# slave-basic.net
KiCad netlist of a schematic drawn in EAGLE
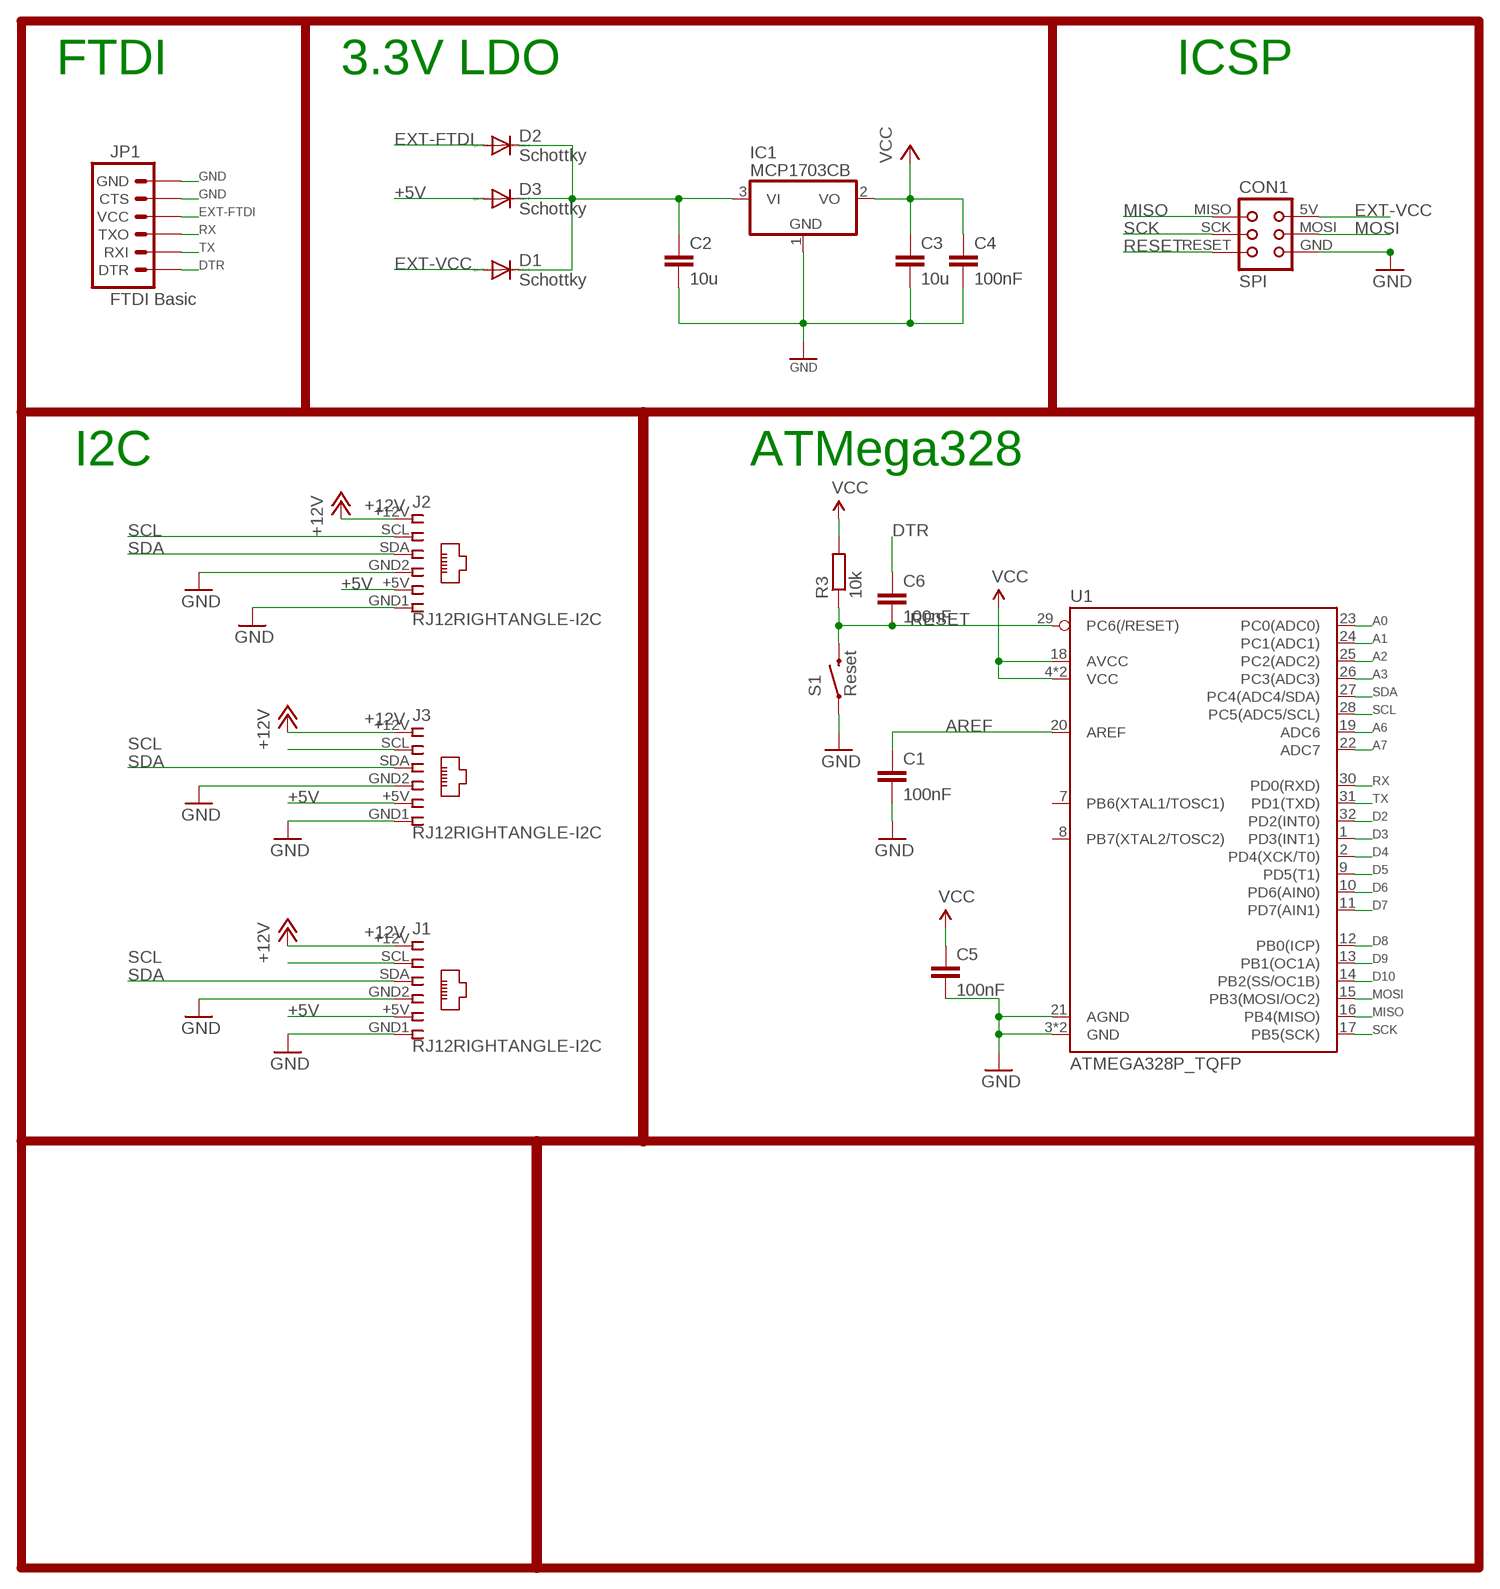
[diagram p0: schematic, sheet 1]

(export (version "E")
  (design (tool "Eeschema 10.0.6"))
  (components
    (comp (ref "C1")
      (value "100nF")
      (footprint "eagle-import:C0805K")
      (fields (field (name "MPN") "80-C1206C104K5R"))
      (libsource (lib "eagle-import") (part "C-EUC0805K"))
    )
    (comp (ref "C2")
      (value "10u")
      (footprint "eagle-import:C0805K")
      (fields (field (name "MPN") "77-VJ1206V106ZXQTBC"))
      (libsource (lib "eagle-import") (part "C-EUC0805K"))
    )
    (comp (ref "C3")
      (value "10u")
      (footprint "eagle-import:C0805K")
      (fields (field (name "MPN") "77-VJ1206V106ZXQTBC"))
      (libsource (lib "eagle-import") (part "C-EUC0805K"))
    )
    (comp (ref "C4")
      (value "100nF")
      (footprint "eagle-import:C0805K")
      (fields (field (name "MPN") "80-C1206C104K5R"))
      (libsource (lib "eagle-import") (part "C-EUC0805K"))
    )
    (comp (ref "C5")
      (value "100nF")
      (footprint "eagle-import:C0805K")
      (fields (field (name "MPN") "80-C1206C104K5R"))
      (libsource (lib "eagle-import") (part "C-EUC0805K"))
    )
    (comp (ref "C6")
      (value "100nF")
      (footprint "eagle-import:C0805K")
      (fields (field (name "MPN") "80-C1206C104K5R"))
      (libsource (lib "eagle-import") (part "C-EUC0805K"))
    )
    (comp (ref "CON1")
      (value "SPI")
      (footprint "eagle-import:TC2030-MCP")
      (libsource (lib "eagle-import") (part "TINYISPTAG"))
    )
    (comp (ref "D1")
      (value "Schottky")
      (footprint "eagle-import:SOD123")
      (fields (field (name "MPN") "621-1N5819HW-F"))
      (libsource (lib "eagle-import") (part "MBR0520LT"))
    )
    (comp (ref "D2")
      (value "Schottky")
      (footprint "eagle-import:SOD123")
      (fields (field (name "MPN") "621-1N5819HW-F"))
      (libsource (lib "eagle-import") (part "MBR0520LT"))
    )
    (comp (ref "D3")
      (value "Schottky")
      (footprint "eagle-import:SOD123")
      (fields (field (name "MPN") "621-1N5819HW-F"))
      (libsource (lib "eagle-import") (part "MBR0520LT"))
    )
    (comp (ref "IC1")
      (value "MCP1703CB")
      (footprint "eagle-import:SOT23")
      (libsource (lib "eagle-import") (part "MCP1703CB"))
    )
    (comp (ref "J1")
      (value "RJ12RIGHTANGLE-I2C")
      (footprint "eagle-import:RJ12-RIGHTANGLE-I2C")
      (libsource (lib "eagle-import") (part "RJ12RIGHTANGLE-I2C"))
    )
    (comp (ref "J2")
      (value "RJ12RIGHTANGLE-I2C")
      (footprint "eagle-import:RJ12-RIGHTANGLE-I2C")
      (libsource (lib "eagle-import") (part "RJ12RIGHTANGLE-I2C"))
    )
    (comp (ref "J3")
      (value "RJ12RIGHTANGLE-I2C")
      (footprint "eagle-import:RJ12-RIGHTANGLE-I2C")
      (libsource (lib "eagle-import") (part "RJ12RIGHTANGLE-I2C"))
    )
    (comp (ref "JP1")
      (value "FTDI Basic")
      (footprint "eagle-import:1X06")
      (libsource (lib "eagle-import") (part "ARDUINO_SERIAL_PROGRAMPTH"))
    )
    (comp (ref "R3")
      (value "10k")
      (footprint "eagle-import:R0805")
      (libsource (lib "eagle-import") (part "R-EU_R0805"))
    )
    (comp (ref "S1")
      (value "Reset")
      (footprint "eagle-import:TACTILE-SWITCH-SMD-ALT01")
      (libsource (lib "eagle-import") (part "SWITCH-MOMENTARY-2SMD-ALT01"))
    )
    (comp (ref "U1")
      (value "ATMEGA328P_TQFP")
      (footprint "eagle-import:TQFP32-08")
      (libsource (lib "eagle-import") (part "ATMEGA328P_TQFP"))
    )
  )
  (nets
    (net (code "1") (name "+12V") (class "Default")
      (node (ref "J1") (pin "+12V") (pinfunction "1_+12V") (pintype "bidirectional"))
      (node (ref "J2") (pin "+12V") (pinfunction "1_+12V") (pintype "bidirectional"))
      (node (ref "J3") (pin "+12V") (pinfunction "1_+12V") (pintype "bidirectional"))
    )
    (net (code "2") (name "/+5V") (class "Default")
      (node (ref "D3") (pin "A") (pinfunction "A_A") (pintype "passive"))
      (node (ref "J1") (pin "+5V") (pinfunction "5_+5V") (pintype "bidirectional"))
      (node (ref "J2") (pin "+5V") (pinfunction "5_+5V") (pintype "bidirectional"))
      (node (ref "J3") (pin "+5V") (pinfunction "5_+5V") (pintype "bidirectional"))
    )
    (net (code "3") (name "/A0") (class "Default")
      (node (ref "U1") (pin "23") (pinfunction "PC0(ADC0)_23") (pintype "bidirectional"))
    )
    (net (code "4") (name "/A1") (class "Default")
      (node (ref "U1") (pin "24") (pinfunction "PC1(ADC1)_24") (pintype "bidirectional"))
    )
    (net (code "5") (name "/A2") (class "Default")
      (node (ref "U1") (pin "25") (pinfunction "PC2(ADC2)_25") (pintype "bidirectional"))
    )
    (net (code "6") (name "/A3") (class "Default")
      (node (ref "U1") (pin "26") (pinfunction "PC3(ADC3)_26") (pintype "bidirectional"))
    )
    (net (code "7") (name "/A6") (class "Default")
      (node (ref "U1") (pin "19") (pinfunction "ADC6_19") (pintype "bidirectional"))
    )
    (net (code "8") (name "/A7") (class "Default")
      (node (ref "U1") (pin "22") (pinfunction "ADC7_22") (pintype "bidirectional"))
    )
    (net (code "9") (name "/AREF") (class "Default")
      (node (ref "C1") (pin "1") (pinfunction "1_1") (pintype "passive"))
      (node (ref "U1") (pin "20") (pinfunction "AREF_20") (pintype "bidirectional"))
    )
    (net (code "10") (name "/D2") (class "Default")
      (node (ref "U1") (pin "32") (pinfunction "PD2(INT0)_32") (pintype "bidirectional"))
    )
    (net (code "11") (name "/D3") (class "Default")
      (node (ref "U1") (pin "1") (pinfunction "PD3(INT1)_1") (pintype "bidirectional"))
    )
    (net (code "12") (name "/D4") (class "Default")
      (node (ref "U1") (pin "2") (pinfunction "PD4(XCK/T0)_2") (pintype "bidirectional"))
    )
    (net (code "13") (name "/D5") (class "Default")
      (node (ref "U1") (pin "9") (pinfunction "PD5(T1)_9") (pintype "bidirectional"))
    )
    (net (code "14") (name "/D6") (class "Default")
      (node (ref "U1") (pin "10") (pinfunction "PD6(AIN0)_10") (pintype "bidirectional"))
    )
    (net (code "15") (name "/D7") (class "Default")
      (node (ref "U1") (pin "11") (pinfunction "PD7(AIN1)_11") (pintype "bidirectional"))
    )
    (net (code "16") (name "/D8") (class "Default")
      (node (ref "U1") (pin "12") (pinfunction "PB0(ICP)_12") (pintype "bidirectional"))
    )
    (net (code "17") (name "/D9") (class "Default")
      (node (ref "U1") (pin "13") (pinfunction "PB1(OC1A)_13") (pintype "bidirectional"))
    )
    (net (code "18") (name "/D10") (class "Default")
      (node (ref "U1") (pin "14") (pinfunction "PB2(SS/OC1B)_14") (pintype "bidirectional"))
    )
    (net (code "19") (name "/DTR") (class "Default")
      (node (ref "C6") (pin "1") (pinfunction "1_1") (pintype "passive"))
      (node (ref "JP1") (pin "1") (pinfunction "DTR_1") (pintype "passive"))
    )
    (net (code "20") (name "/EXT-FTDI") (class "Default")
      (node (ref "D2") (pin "A") (pinfunction "A_A") (pintype "passive"))
      (node (ref "JP1") (pin "4") (pinfunction "VCC_4") (pintype "passive"))
    )
    (net (code "21") (name "/EXT-VCC") (class "Default")
      (node (ref "CON1") (pin "5V") (pinfunction "VCC_5V") (pintype "passive"))
      (node (ref "D1") (pin "A") (pinfunction "A_A") (pintype "passive"))
    )
    (net (code "22") (name "/MISO") (class "Default")
      (node (ref "CON1") (pin "MISO") (pinfunction "MISO_MISO") (pintype "passive"))
      (node (ref "U1") (pin "16") (pinfunction "PB4(MISO)_16") (pintype "bidirectional"))
    )
    (net (code "23") (name "/MOSI") (class "Default")
      (node (ref "CON1") (pin "MOSI") (pinfunction "MOSI_MOSI") (pintype "passive"))
      (node (ref "U1") (pin "15") (pinfunction "PB3(MOSI/OC2)_15") (pintype "bidirectional"))
    )
    (net (code "24") (name "/RESET") (class "Default")
      (node (ref "C6") (pin "2") (pinfunction "2_2") (pintype "passive"))
      (node (ref "CON1") (pin "RESET") (pinfunction "RESET_RESET") (pintype "passive"))
      (node (ref "R3") (pin "1") (pinfunction "1_1") (pintype "passive"))
      (node (ref "S1") (pin "3") (pinfunction "2_3") (pintype "passive"))
      (node (ref "S1") (pin "4") (pinfunction "2_4") (pintype "passive"))
      (node (ref "U1") (pin "29") (pinfunction "PC6(/RESET)_29") (pintype "bidirectional"))
    )
    (net (code "25") (name "/RX") (class "Default")
      (node (ref "JP1") (pin "3") (pinfunction "TXO_3") (pintype "passive"))
      (node (ref "U1") (pin "30") (pinfunction "PD0(RXD)_30") (pintype "bidirectional"))
    )
    (net (code "26") (name "/SCK") (class "Default")
      (node (ref "CON1") (pin "SCK") (pinfunction "SCK_SCK") (pintype "passive"))
      (node (ref "U1") (pin "17") (pinfunction "PB5(SCK)_17") (pintype "bidirectional"))
    )
    (net (code "27") (name "/SCL") (class "Default")
      (node (ref "J1") (pin "SCL") (pinfunction "2_SCL") (pintype "bidirectional"))
      (node (ref "J2") (pin "SCL") (pinfunction "2_SCL") (pintype "bidirectional"))
      (node (ref "J3") (pin "SCL") (pinfunction "2_SCL") (pintype "bidirectional"))
      (node (ref "U1") (pin "28") (pinfunction "PC5(ADC5/SCL)_28") (pintype "bidirectional"))
    )
    (net (code "28") (name "/SDA") (class "Default")
      (node (ref "J1") (pin "SDA") (pinfunction "3_SDA") (pintype "bidirectional"))
      (node (ref "J2") (pin "SDA") (pinfunction "3_SDA") (pintype "bidirectional"))
      (node (ref "J3") (pin "SDA") (pinfunction "3_SDA") (pintype "bidirectional"))
      (node (ref "U1") (pin "27") (pinfunction "PC4(ADC4/SDA)_27") (pintype "bidirectional"))
    )
    (net (code "29") (name "/TX") (class "Default")
      (node (ref "JP1") (pin "2") (pinfunction "RXI_2") (pintype "passive"))
      (node (ref "U1") (pin "31") (pinfunction "PD1(TXD)_31") (pintype "bidirectional"))
    )
    (net (code "30") (name "GND") (class "Default")
      (node (ref "C1") (pin "2") (pinfunction "2_2") (pintype "passive"))
      (node (ref "C2") (pin "2") (pinfunction "2_2") (pintype "passive"))
      (node (ref "C3") (pin "2") (pinfunction "2_2") (pintype "passive"))
      (node (ref "C4") (pin "2") (pinfunction "2_2") (pintype "passive"))
      (node (ref "C5") (pin "2") (pinfunction "2_2") (pintype "passive"))
      (node (ref "CON1") (pin "GND") (pinfunction "GND_GND") (pintype "passive"))
      (node (ref "IC1") (pin "1") (pinfunction "GND_1") (pintype "passive"))
      (node (ref "J1") (pin "GND1") (pinfunction "6_GND1") (pintype "bidirectional"))
      (node (ref "J1") (pin "GND2") (pinfunction "4_GND2") (pintype "bidirectional"))
      (node (ref "J2") (pin "GND1") (pinfunction "6_GND1") (pintype "bidirectional"))
      (node (ref "J2") (pin "GND2") (pinfunction "4_GND2") (pintype "bidirectional"))
      (node (ref "J3") (pin "GND1") (pinfunction "6_GND1") (pintype "bidirectional"))
      (node (ref "J3") (pin "GND2") (pinfunction "4_GND2") (pintype "bidirectional"))
      (node (ref "JP1") (pin "5") (pinfunction "CTS_5") (pintype "passive"))
      (node (ref "JP1") (pin "6") (pinfunction "GND_6") (pintype "passive"))
      (node (ref "S1") (pin "1") (pinfunction "1_1") (pintype "passive"))
      (node (ref "S1") (pin "2") (pinfunction "1_2") (pintype "passive"))
      (node (ref "U1") (pin "21") (pinfunction "AGND_21") (pintype "bidirectional"))
      (node (ref "U1") (pin "3") (pinfunction "GND_3") (pintype "bidirectional"))
      (node (ref "U1") (pin "5") (pinfunction "GND_5") (pintype "bidirectional"))
    )
    (net (code "31") (name "Net-(IC1-VI)") (class "Default")
      (node (ref "C2") (pin "1") (pinfunction "1_1") (pintype "passive"))
      (node (ref "D1") (pin "C") (pinfunction "C_C") (pintype "passive"))
      (node (ref "D2") (pin "C") (pinfunction "C_C") (pintype "passive"))
      (node (ref "D3") (pin "C") (pinfunction "C_C") (pintype "passive"))
      (node (ref "IC1") (pin "3") (pinfunction "VI_3") (pintype "input"))
    )
    (net (code "32") (name "VCC") (class "Default")
      (node (ref "C3") (pin "1") (pinfunction "1_1") (pintype "passive"))
      (node (ref "C4") (pin "1") (pinfunction "1_1") (pintype "passive"))
      (node (ref "C5") (pin "1") (pinfunction "1_1") (pintype "passive"))
      (node (ref "IC1") (pin "2") (pinfunction "VO_2") (pintype "passive"))
      (node (ref "R3") (pin "2") (pinfunction "2_2") (pintype "passive"))
      (node (ref "U1") (pin "18") (pinfunction "AVCC_18") (pintype "bidirectional"))
      (node (ref "U1") (pin "4") (pinfunction "VCC_4") (pintype "bidirectional"))
      (node (ref "U1") (pin "6") (pinfunction "VCC_6") (pintype "bidirectional"))
    )
    (net (code "33") (name "unconnected-(U1-PB6(XTAL1{slash}TOSC1)-Pad7)") (class "Default")
      (node (ref "U1") (pin "7") (pinfunction "PB6(XTAL1/TOSC1)_7") (pintype "bidirectional"))
    )
    (net (code "34") (name "unconnected-(U1-PB7(XTAL2{slash}TOSC2)-Pad8)") (class "Default")
      (node (ref "U1") (pin "8") (pinfunction "PB7(XTAL2/TOSC2)_8") (pintype "bidirectional"))
    )
  )
)
